# 16F7167segadc.net
KiCad netlist of a schematic drawn in EAGLE
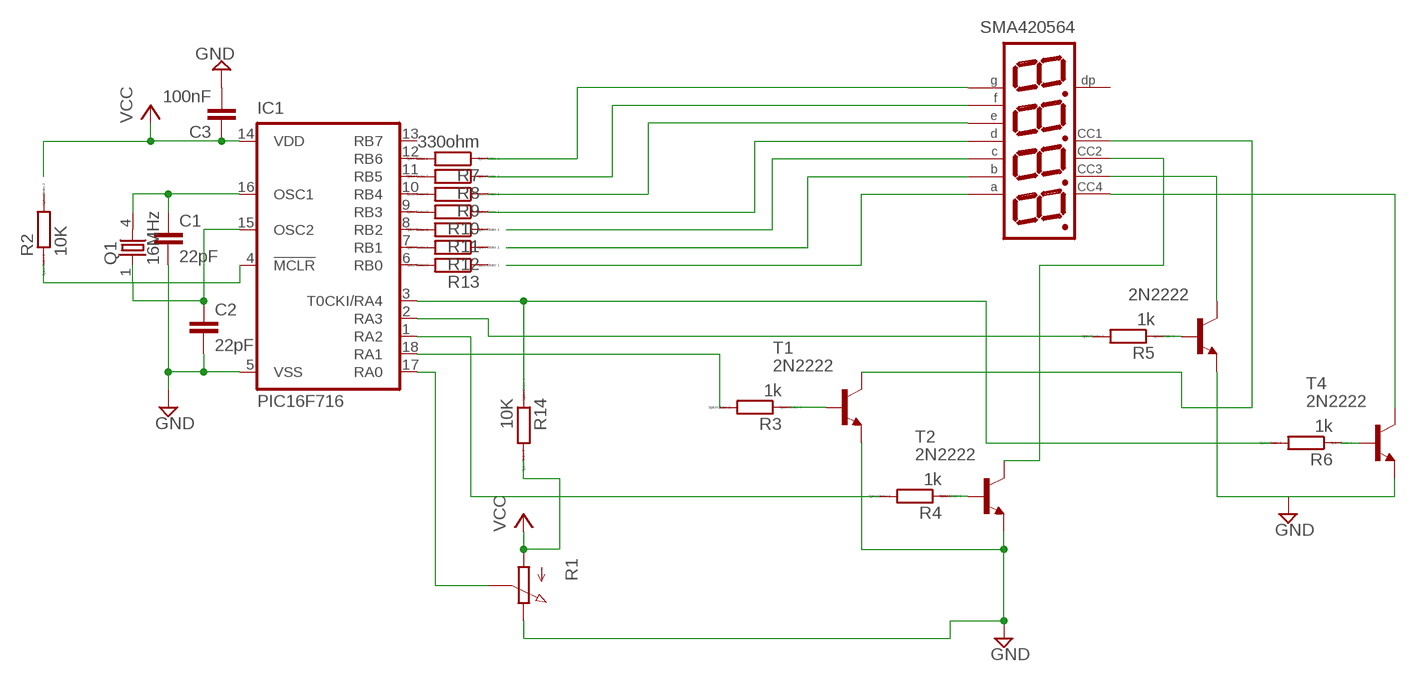
[diagram p0: schematic, sheet 1]

(export (version "E")
  (design (tool "Eeschema 10.0.6"))
  (components
    (comp (ref "C1")
      (value "22pF")
      (footprint "eagle-import:C2.5-3")
      (libsource (lib "eagle-import") (part "C2,5-3"))
    )
    (comp (ref "C2")
      (value "22pF")
      (footprint "eagle-import:C2.5-3")
      (libsource (lib "eagle-import") (part "C2,5-3"))
    )
    (comp (ref "C3")
      (value "100nF")
      (footprint "eagle-import:C2.5-3")
      (libsource (lib "eagle-import") (part "C2,5-3"))
    )
    (comp (ref "IC1")
      (value "PIC16F716")
      (footprint "eagle-import:DIL18")
      (libsource (lib "eagle-import") (part "PIC16F8P3"))
    )
    (comp (ref "Q1")
      (value "16MHz")
      (footprint "eagle-import:86SMX")
      (fields (field (name "MF") "C-MAC  FREQUENCY PRODUCTS LTD") (field (name "MPN") "XTAL003321- 86SMX"))
      (libsource (lib "eagle-import") (part "86SMX"))
    )
    (comp (ref "R1")
      (value "PC25")
      (footprint "eagle-import:PC25")
      (fields (field (name "MF") "CLAROSTAT") (field (name "MPN") "308NPC25KS"))
      (libsource (lib "eagle-import") (part "PC25"))
    )
    (comp (ref "R2")
      (value "10K")
      (footprint "eagle-import:0204_7")
      (libsource (lib "eagle-import") (part "R0204/7"))
    )
    (comp (ref "R3")
      (value "1k")
      (footprint "eagle-import:0204_7")
      (libsource (lib "eagle-import") (part "R0204/7"))
    )
    (comp (ref "R4")
      (value "1k")
      (footprint "eagle-import:0204_7")
      (libsource (lib "eagle-import") (part "R0204/7"))
    )
    (comp (ref "R5")
      (value "1k")
      (footprint "eagle-import:0204_7")
      (libsource (lib "eagle-import") (part "R0204/7"))
    )
    (comp (ref "R6")
      (value "1k")
      (footprint "eagle-import:0204_7")
      (libsource (lib "eagle-import") (part "R0204/7"))
    )
    (comp (ref "R7")
      (value "330ohm")
      (footprint "eagle-import:0204_7")
      (libsource (lib "eagle-import") (part "R0204/7"))
    )
    (comp (ref "R8")
      (value "R0204/7")
      (footprint "eagle-import:0204_7")
      (libsource (lib "eagle-import") (part "R0204/7"))
    )
    (comp (ref "R9")
      (value "R0204/7")
      (footprint "eagle-import:0204_7")
      (libsource (lib "eagle-import") (part "R0204/7"))
    )
    (comp (ref "R10")
      (value "R0204/7")
      (footprint "eagle-import:0204_7")
      (libsource (lib "eagle-import") (part "R0204/7"))
    )
    (comp (ref "R11")
      (value "R0204/7")
      (footprint "eagle-import:0204_7")
      (libsource (lib "eagle-import") (part "R0204/7"))
    )
    (comp (ref "R12")
      (value "R0204/7")
      (footprint "eagle-import:0204_7")
      (libsource (lib "eagle-import") (part "R0204/7"))
    )
    (comp (ref "R13")
      (value "R0204/7")
      (footprint "eagle-import:0204_7")
      (libsource (lib "eagle-import") (part "R0204/7"))
    )
    (comp (ref "R14")
      (value "10K")
      (footprint "eagle-import:0204_7")
      (libsource (lib "eagle-import") (part "R0204/7"))
    )
    (comp (ref "SMA420564")
      (value "NFD-5641AS")
      (footprint "eagle-import:NFD-5641")
      (libsource (lib "eagle-import") (part "NFD-5641AS"))
    )
    (comp (ref "T1")
      (value "2N2222")
      (footprint "eagle-import:TO18")
      (libsource (lib "eagle-import") (part "2N2222"))
    )
    (comp (ref "T2")
      (value "2N2222")
      (footprint "eagle-import:TO18")
      (libsource (lib "eagle-import") (part "2N2222"))
    )
    (comp (ref "T3")
      (value "2N2222")
      (footprint "eagle-import:TO18")
      (libsource (lib "eagle-import") (part "2N2222"))
    )
    (comp (ref "T4")
      (value "2N2222")
      (footprint "eagle-import:TO18")
      (libsource (lib "eagle-import") (part "2N2222"))
    )
  )
  (nets
    (net (code "1") (name "GND") (class "Default")
      (node (ref "C1") (pin "2") (pinfunction "2_2") (pintype "passive"))
      (node (ref "C2") (pin "2") (pinfunction "2_2") (pintype "passive"))
      (node (ref "C3") (pin "2") (pinfunction "2_2") (pintype "passive"))
      (node (ref "IC1") (pin "5") (pinfunction "VSS_5") (pintype "power_in"))
      (node (ref "R1") (pin "E") (pinfunction "E_E") (pintype "passive"))
      (node (ref "T1") (pin "1") (pinfunction "E_1") (pintype "passive"))
      (node (ref "T2") (pin "1") (pinfunction "E_1") (pintype "passive"))
      (node (ref "T3") (pin "1") (pinfunction "E_1") (pintype "passive"))
      (node (ref "T4") (pin "1") (pinfunction "E_1") (pintype "passive"))
    )
    (net (code "2") (name "Net-(IC1-OSC1)") (class "Default")
      (node (ref "C1") (pin "1") (pinfunction "1_1") (pintype "passive"))
      (node (ref "IC1") (pin "16") (pinfunction "OSC1_16") (pintype "input"))
      (node (ref "Q1") (pin "4") (pinfunction "2_4") (pintype "passive"))
    )
    (net (code "3") (name "Net-(IC1-OSC2)") (class "Default")
      (node (ref "C2") (pin "1") (pinfunction "1_1") (pintype "passive"))
      (node (ref "IC1") (pin "15") (pinfunction "OSC2_15") (pintype "output"))
      (node (ref "Q1") (pin "1") (pinfunction "1_1") (pintype "passive"))
    )
    (net (code "4") (name "Net-(IC1-RA0)") (class "Default")
      (node (ref "IC1") (pin "17") (pinfunction "RA0_17") (pintype "bidirectional"))
      (node (ref "R1") (pin "S") (pinfunction "S_S") (pintype "passive"))
    )
    (net (code "5") (name "Net-(IC1-RA1)") (class "Default")
      (node (ref "IC1") (pin "18") (pinfunction "RA1_18") (pintype "bidirectional"))
      (node (ref "R3") (pin "2") (pinfunction "2_2") (pintype "passive"))
    )
    (net (code "6") (name "Net-(IC1-RA2)") (class "Default")
      (node (ref "IC1") (pin "1") (pinfunction "RA2_1") (pintype "bidirectional"))
      (node (ref "R4") (pin "2") (pinfunction "2_2") (pintype "passive"))
    )
    (net (code "7") (name "Net-(IC1-RA3)") (class "Default")
      (node (ref "IC1") (pin "2") (pinfunction "RA3_2") (pintype "bidirectional"))
      (node (ref "R5") (pin "2") (pinfunction "2_2") (pintype "passive"))
    )
    (net (code "8") (name "Net-(IC1-RB0)") (class "Default")
      (node (ref "IC1") (pin "6") (pinfunction "RB0_6") (pintype "bidirectional"))
      (node (ref "R13") (pin "2") (pinfunction "2_2") (pintype "passive"))
    )
    (net (code "9") (name "Net-(IC1-RB1)") (class "Default")
      (node (ref "IC1") (pin "7") (pinfunction "RB1_7") (pintype "bidirectional"))
      (node (ref "R12") (pin "2") (pinfunction "2_2") (pintype "passive"))
    )
    (net (code "10") (name "Net-(IC1-RB2)") (class "Default")
      (node (ref "IC1") (pin "8") (pinfunction "RB2_8") (pintype "bidirectional"))
      (node (ref "R11") (pin "2") (pinfunction "2_2") (pintype "passive"))
    )
    (net (code "11") (name "Net-(IC1-RB3)") (class "Default")
      (node (ref "IC1") (pin "9") (pinfunction "RB3_9") (pintype "bidirectional"))
      (node (ref "R10") (pin "2") (pinfunction "2_2") (pintype "passive"))
    )
    (net (code "12") (name "Net-(IC1-RB4)") (class "Default")
      (node (ref "IC1") (pin "10") (pinfunction "RB4_10") (pintype "bidirectional"))
      (node (ref "R9") (pin "2") (pinfunction "2_2") (pintype "passive"))
    )
    (net (code "13") (name "Net-(IC1-RB5)") (class "Default")
      (node (ref "IC1") (pin "11") (pinfunction "RB5_11") (pintype "bidirectional"))
      (node (ref "R8") (pin "2") (pinfunction "2_2") (pintype "passive"))
    )
    (net (code "14") (name "Net-(IC1-RB6)") (class "Default")
      (node (ref "IC1") (pin "12") (pinfunction "RB6_12") (pintype "bidirectional"))
      (node (ref "R7") (pin "2") (pinfunction "2_2") (pintype "passive"))
    )
    (net (code "15") (name "Net-(IC1-T0CKI{slash}RA4)") (class "Default")
      (node (ref "IC1") (pin "3") (pinfunction "T0CKI/RA4_3") (pintype "bidirectional"))
      (node (ref "R14") (pin "1") (pinfunction "1_1") (pintype "passive"))
      (node (ref "R6") (pin "2") (pinfunction "2_2") (pintype "passive"))
    )
    (net (code "16") (name "Net-(IC1-~{MCLR})") (class "Default")
      (node (ref "IC1") (pin "4") (pinfunction "~{MCLR}_4") (pintype "input"))
      (node (ref "R2") (pin "1") (pinfunction "1_1") (pintype "passive"))
    )
    (net (code "17") (name "Net-(R7-Pad1)") (class "Default")
      (node (ref "R7") (pin "1") (pinfunction "1_1") (pintype "passive"))
      (node (ref "SMA420564") (pin "P$5") (pinfunction "P$5_P$5") (pintype "bidirectional"))
    )
    (net (code "18") (name "Net-(R8-Pad1)") (class "Default")
      (node (ref "R8") (pin "1") (pinfunction "1_1") (pintype "passive"))
      (node (ref "SMA420564") (pin "P$10") (pinfunction "P$10_P$10") (pintype "bidirectional"))
    )
    (net (code "19") (name "Net-(R9-Pad1)") (class "Default")
      (node (ref "R9") (pin "1") (pinfunction "1_1") (pintype "passive"))
      (node (ref "SMA420564") (pin "P$1") (pinfunction "P$1_P$1") (pintype "bidirectional"))
    )
    (net (code "20") (name "Net-(R10-Pad1)") (class "Default")
      (node (ref "R10") (pin "1") (pinfunction "1_1") (pintype "passive"))
      (node (ref "SMA420564") (pin "P$2") (pinfunction "P$2_P$2") (pintype "bidirectional"))
    )
    (net (code "21") (name "Net-(T1-B)") (class "Default")
      (node (ref "R3") (pin "1") (pinfunction "1_1") (pintype "passive"))
      (node (ref "T1") (pin "2") (pinfunction "B_2") (pintype "passive"))
    )
    (net (code "22") (name "Net-(T1-C)") (class "Default")
      (node (ref "SMA420564") (pin "P$12") (pinfunction "P$12_P$12") (pintype "bidirectional"))
      (node (ref "T1") (pin "3") (pinfunction "C_3") (pintype "passive"))
    )
    (net (code "23") (name "Net-(T2-B)") (class "Default")
      (node (ref "R4") (pin "1") (pinfunction "1_1") (pintype "passive"))
      (node (ref "T2") (pin "2") (pinfunction "B_2") (pintype "passive"))
    )
    (net (code "24") (name "Net-(T2-C)") (class "Default")
      (node (ref "SMA420564") (pin "P$9") (pinfunction "P$9_P$9") (pintype "bidirectional"))
      (node (ref "T2") (pin "3") (pinfunction "C_3") (pintype "passive"))
    )
    (net (code "25") (name "Net-(T3-B)") (class "Default")
      (node (ref "R5") (pin "1") (pinfunction "1_1") (pintype "passive"))
      (node (ref "T3") (pin "2") (pinfunction "B_2") (pintype "passive"))
    )
    (net (code "26") (name "Net-(T3-C)") (class "Default")
      (node (ref "SMA420564") (pin "P$8") (pinfunction "P$8_P$8") (pintype "bidirectional"))
      (node (ref "T3") (pin "3") (pinfunction "C_3") (pintype "passive"))
    )
    (net (code "27") (name "Net-(T4-B)") (class "Default")
      (node (ref "R6") (pin "1") (pinfunction "1_1") (pintype "passive"))
      (node (ref "T4") (pin "2") (pinfunction "B_2") (pintype "passive"))
    )
    (net (code "28") (name "Net-(T4-C)") (class "Default")
      (node (ref "SMA420564") (pin "P$6") (pinfunction "P$6_P$6") (pintype "bidirectional"))
      (node (ref "T4") (pin "3") (pinfunction "C_3") (pintype "passive"))
    )
    (net (code "29") (name "VCC") (class "Default")
      (node (ref "C3") (pin "1") (pinfunction "1_1") (pintype "passive"))
      (node (ref "IC1") (pin "14") (pinfunction "VDD_14") (pintype "power_in"))
      (node (ref "R1") (pin "A") (pinfunction "A_A") (pintype "passive"))
      (node (ref "R14") (pin "2") (pinfunction "2_2") (pintype "passive"))
    )
    (net (code "30") (name "unconnected-(IC1-RB7-Pad13)") (class "Default")
      (node (ref "IC1") (pin "13") (pinfunction "RB7_13") (pintype "bidirectional"))
    )
    (net (code "31") (name "unconnected-(R2-Pad2)") (class "Default")
      (node (ref "R2") (pin "2") (pinfunction "2_2") (pintype "passive"))
    )
    (net (code "32") (name "unconnected-(R11-Pad1)") (class "Default")
      (node (ref "R11") (pin "1") (pinfunction "1_1") (pintype "passive"))
    )
    (net (code "33") (name "unconnected-(R12-Pad1)") (class "Default")
      (node (ref "R12") (pin "1") (pinfunction "1_1") (pintype "passive"))
    )
    (net (code "34") (name "unconnected-(R13-Pad1)") (class "Default")
      (node (ref "R13") (pin "1") (pinfunction "1_1") (pintype "passive"))
    )
    (net (code "35") (name "unconnected-(SMA420564-PadP$3)") (class "Default")
      (node (ref "SMA420564") (pin "P$3") (pinfunction "P$3_P$3") (pintype "bidirectional"))
    )
    (net (code "36") (name "unconnected-(SMA420564-PadP$4)") (class "Default")
      (node (ref "SMA420564") (pin "P$4") (pinfunction "P$4_P$4") (pintype "bidirectional"))
    )
    (net (code "37") (name "unconnected-(SMA420564-PadP$7)") (class "Default")
      (node (ref "SMA420564") (pin "P$7") (pinfunction "P$7_P$7") (pintype "bidirectional"))
    )
    (net (code "38") (name "unconnected-(SMA420564-PadP$11)") (class "Default")
      (node (ref "SMA420564") (pin "P$11") (pinfunction "P$11_P$11") (pintype "bidirectional"))
    )
  )
)
